# sensores.net
KiCad netlist of a schematic drawn in EAGLE
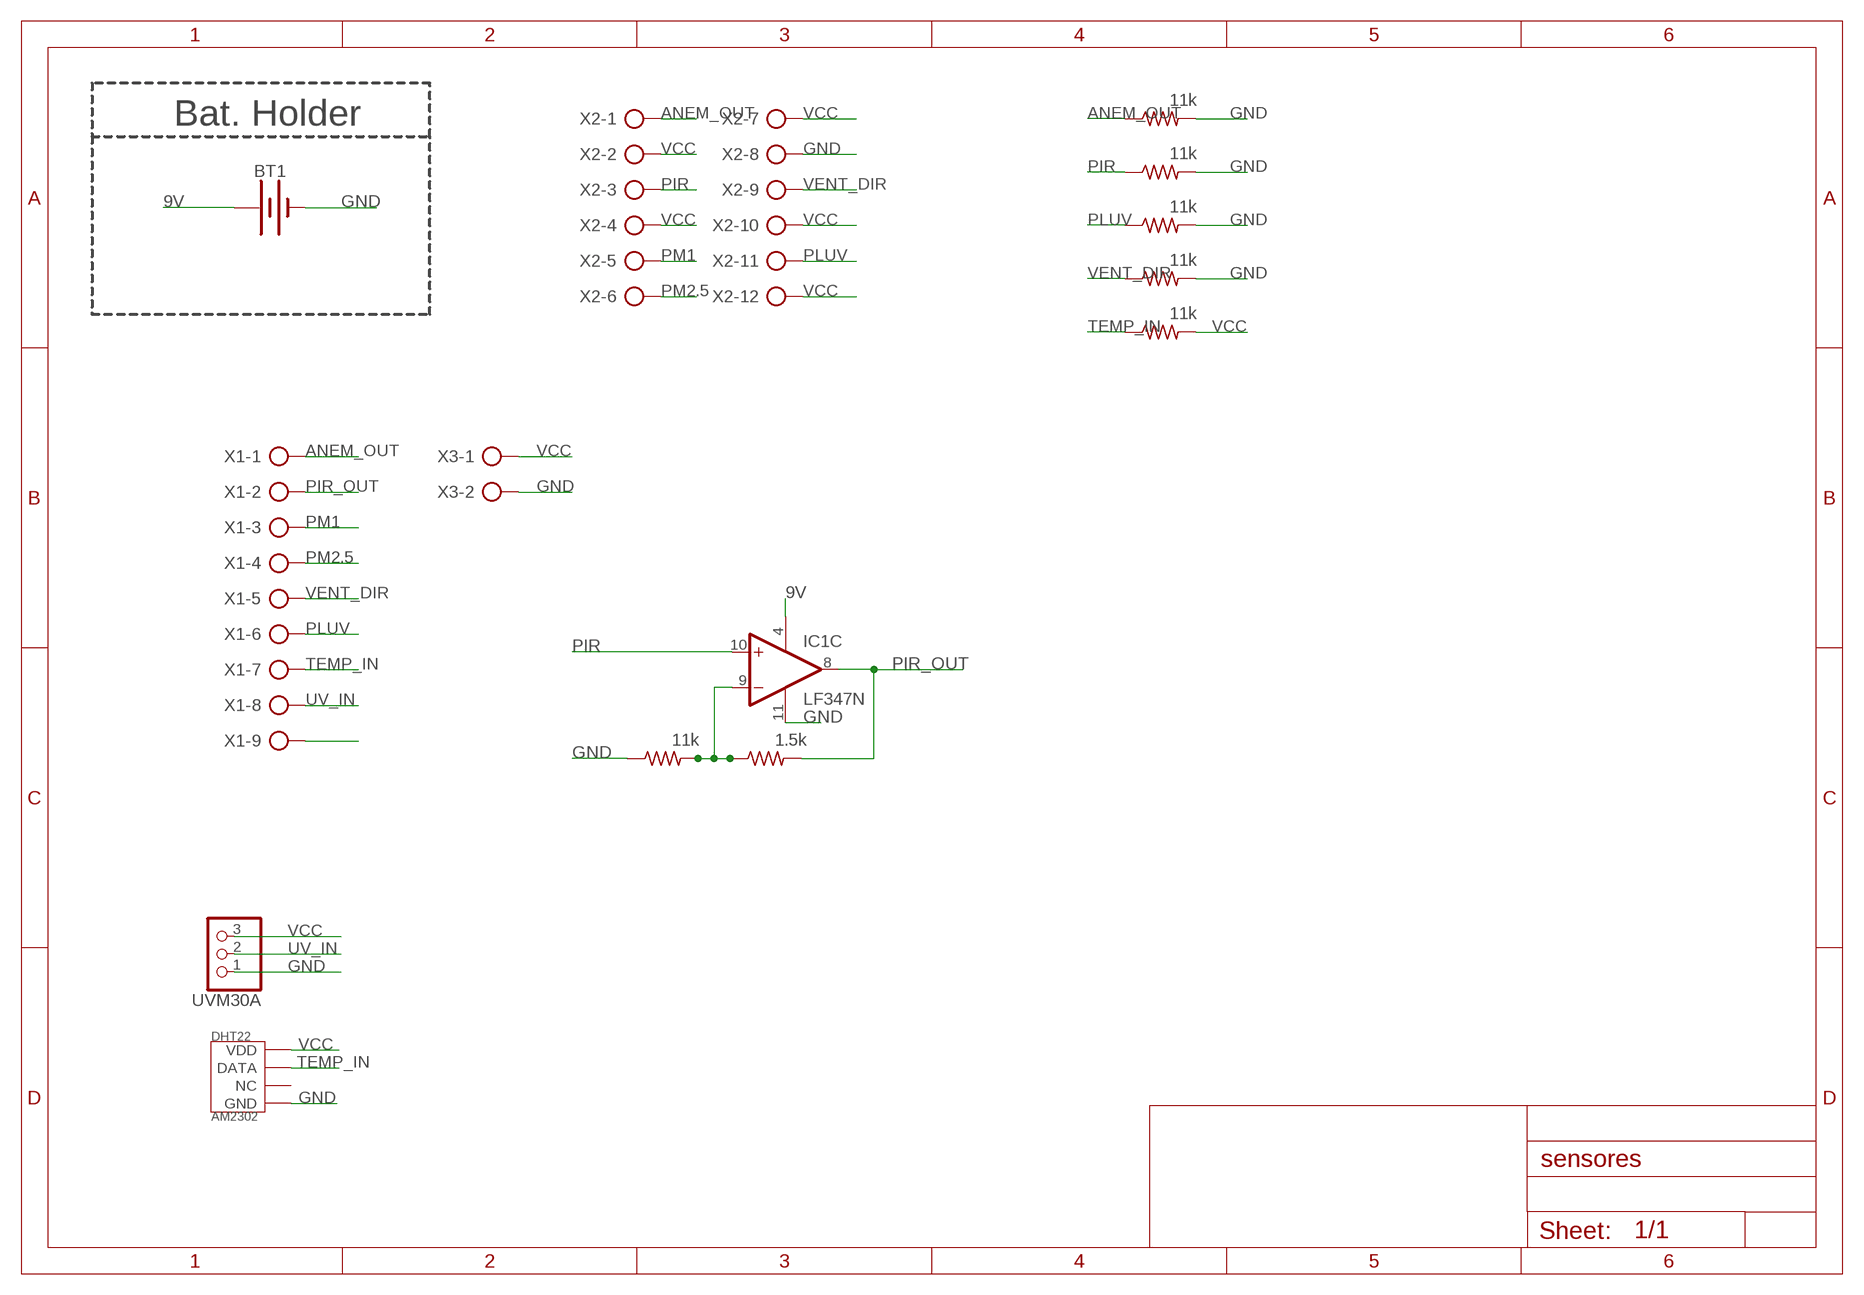
[diagram p0: schematic, sheet 1]

(export (version "E")
  (design (tool "Eeschema 10.0.6"))
  (components
    (comp (ref "BT1")
      (value "BATTERY-9V")
      (footprint "eagle-import:BATTCON_9V")
      (libsource (lib "eagle-import") (part "BATTERY-9V"))
    )
    (comp (ref "DHT22")
      (value "AM2302")
      (footprint "eagle-import:SNR4-2.54-25.0X15.0X7.0MM")
      (libsource (lib "eagle-import") (part "TEM-HUM-AM2302(4P-25.0X15.0MM)"))
    )
    (comp (ref "IC1")
      (value "LF347N")
      (footprint "eagle-import:DIL14")
      (libsource (lib "eagle-import") (part "LF347N"))
    )
    (comp (ref "R1")
      (value "11k")
      (footprint "eagle-import:0204_7")
      (libsource (lib "eagle-import") (part "R-US_0204/7"))
    )
    (comp (ref "R2")
      (value "1.5k")
      (footprint "eagle-import:0204_7")
      (libsource (lib "eagle-import") (part "R-US_0204/7"))
    )
    (comp (ref "R3")
      (value "11k")
      (footprint "eagle-import:0204_7")
      (libsource (lib "eagle-import") (part "R-US_0204/7"))
    )
    (comp (ref "R4")
      (value "11k")
      (footprint "eagle-import:0204_7")
      (libsource (lib "eagle-import") (part "R-US_0204/7"))
    )
    (comp (ref "R5")
      (value "11k")
      (footprint "eagle-import:0204_7")
      (libsource (lib "eagle-import") (part "R-US_0204/7"))
    )
    (comp (ref "R6")
      (value "11k")
      (footprint "eagle-import:0204_7")
      (libsource (lib "eagle-import") (part "R-US_0204/7"))
    )
    (comp (ref "R7")
      (value "11k")
      (footprint "eagle-import:0204_7")
      (libsource (lib "eagle-import") (part "R-US_0204/7"))
    )
    (comp (ref "UVM30A")
      (value "PINHD-1X3/90")
      (footprint "eagle-import:1X03_90")
      (libsource (lib "eagle-import") (part "PINHD-1X3/90"))
    )
    (comp (ref "X1")
      (value "AK500/9")
      (footprint "eagle-import:AK500_9")
      (libsource (lib "eagle-import") (part "AK500/9"))
    )
    (comp (ref "X2")
      (value "AK500/12")
      (footprint "eagle-import:AK500_12")
      (libsource (lib "eagle-import") (part "AK500/12"))
    )
    (comp (ref "X3")
      (value "AK500/2")
      (footprint "eagle-import:AK500_2")
      (libsource (lib "eagle-import") (part "AK500/2"))
    )
  )
  (nets
    (net (code "1") (name "/9V") (class "Default")
      (node (ref "BT1") (pin "+") (pinfunction "+_+") (pintype "power_in"))
      (node (ref "IC1") (pin "4") (pinfunction "V+_4") (pintype "power_in"))
    )
    (net (code "2") (name "/ANEM_OUT") (class "Default")
      (node (ref "R3") (pin "1") (pinfunction "1_1") (pintype "passive"))
      (node (ref "X1") (pin "1") (pinfunction "KL_1") (pintype "passive"))
      (node (ref "X2") (pin "1") (pinfunction "KL_1") (pintype "passive"))
    )
    (net (code "3") (name "/GND") (class "Default")
      (node (ref "BT1") (pin "-") (pinfunction "-_-") (pintype "power_in"))
      (node (ref "DHT22") (pin "P$4") (pinfunction "GND_P$4") (pintype "power_in"))
      (node (ref "IC1") (pin "11") (pinfunction "V-_11") (pintype "power_in"))
      (node (ref "R1") (pin "1") (pinfunction "1_1") (pintype "passive"))
      (node (ref "R3") (pin "2") (pinfunction "2_2") (pintype "passive"))
      (node (ref "R4") (pin "2") (pinfunction "2_2") (pintype "passive"))
      (node (ref "R5") (pin "2") (pinfunction "2_2") (pintype "passive"))
      (node (ref "R6") (pin "2") (pinfunction "2_2") (pintype "passive"))
      (node (ref "UVM30A") (pin "1") (pinfunction "1_1") (pintype "passive"))
      (node (ref "X2") (pin "8") (pinfunction "KL_8") (pintype "passive"))
      (node (ref "X3") (pin "2") (pinfunction "KL_2") (pintype "passive"))
    )
    (net (code "4") (name "/PIR") (class "Default")
      (node (ref "IC1") (pin "10") (pinfunction "+IN_10") (pintype "input"))
      (node (ref "R4") (pin "1") (pinfunction "1_1") (pintype "passive"))
      (node (ref "X2") (pin "3") (pinfunction "KL_3") (pintype "passive"))
    )
    (net (code "5") (name "/PIR_OUT") (class "Default")
      (node (ref "IC1") (pin "8") (pinfunction "OUT_8") (pintype "output"))
      (node (ref "R2") (pin "2") (pinfunction "2_2") (pintype "passive"))
      (node (ref "X1") (pin "2") (pinfunction "KL_2") (pintype "passive"))
    )
    (net (code "6") (name "/PLUV") (class "Default")
      (node (ref "R5") (pin "1") (pinfunction "1_1") (pintype "passive"))
      (node (ref "X1") (pin "6") (pinfunction "KL_6") (pintype "passive"))
      (node (ref "X2") (pin "11") (pinfunction "KL_11") (pintype "passive"))
    )
    (net (code "7") (name "/PM1") (class "Default")
      (node (ref "X1") (pin "3") (pinfunction "KL_3") (pintype "passive"))
      (node (ref "X2") (pin "5") (pinfunction "KL_5") (pintype "passive"))
    )
    (net (code "8") (name "/PM2.5") (class "Default")
      (node (ref "X1") (pin "4") (pinfunction "KL_4") (pintype "passive"))
      (node (ref "X2") (pin "6") (pinfunction "KL_6") (pintype "passive"))
    )
    (net (code "9") (name "/TEMP_IN") (class "Default")
      (node (ref "DHT22") (pin "P$2") (pinfunction "DATA_P$2") (pintype "bidirectional"))
      (node (ref "R7") (pin "1") (pinfunction "1_1") (pintype "passive"))
      (node (ref "X1") (pin "7") (pinfunction "KL_7") (pintype "passive"))
    )
    (net (code "10") (name "/UV_IN") (class "Default")
      (node (ref "UVM30A") (pin "2") (pinfunction "2_2") (pintype "passive"))
      (node (ref "X1") (pin "8") (pinfunction "KL_8") (pintype "passive"))
    )
    (net (code "11") (name "/VCC") (class "Default")
      (node (ref "DHT22") (pin "P$1") (pinfunction "VDD_P$1") (pintype "power_in"))
      (node (ref "R7") (pin "2") (pinfunction "2_2") (pintype "passive"))
      (node (ref "UVM30A") (pin "3") (pinfunction "3_3") (pintype "passive"))
      (node (ref "X2") (pin "10") (pinfunction "KL_10") (pintype "passive"))
      (node (ref "X2") (pin "12") (pinfunction "KL_12") (pintype "passive"))
      (node (ref "X2") (pin "2") (pinfunction "KL_2") (pintype "passive"))
      (node (ref "X2") (pin "4") (pinfunction "KL_4") (pintype "passive"))
      (node (ref "X2") (pin "7") (pinfunction "KL_7") (pintype "passive"))
      (node (ref "X3") (pin "1") (pinfunction "KL_1") (pintype "passive"))
    )
    (net (code "12") (name "/VENT_DIR") (class "Default")
      (node (ref "R6") (pin "1") (pinfunction "1_1") (pintype "passive"))
      (node (ref "X1") (pin "5") (pinfunction "KL_5") (pintype "passive"))
      (node (ref "X2") (pin "9") (pinfunction "KL_9") (pintype "passive"))
    )
    (net (code "13") (name "Net-(IC1C--IN)") (class "Default")
      (node (ref "IC1") (pin "9") (pinfunction "-IN_9") (pintype "input"))
      (node (ref "R1") (pin "2") (pinfunction "2_2") (pintype "passive"))
      (node (ref "R2") (pin "1") (pinfunction "1_1") (pintype "passive"))
    )
    (net (code "14") (name "unconnected-(DHT22-NC-PadP$3)") (class "Default")
      (node (ref "DHT22") (pin "P$3") (pinfunction "NC_P$3") (pintype "no_connect"))
    )
    (net (code "15") (name "unconnected-(X1I-KL-Pad9)") (class "Default")
      (node (ref "X1") (pin "9") (pinfunction "KL_9") (pintype "passive"))
    )
  )
)
